# Power19V.net
KiCad netlist of a schematic drawn in Altium Designer
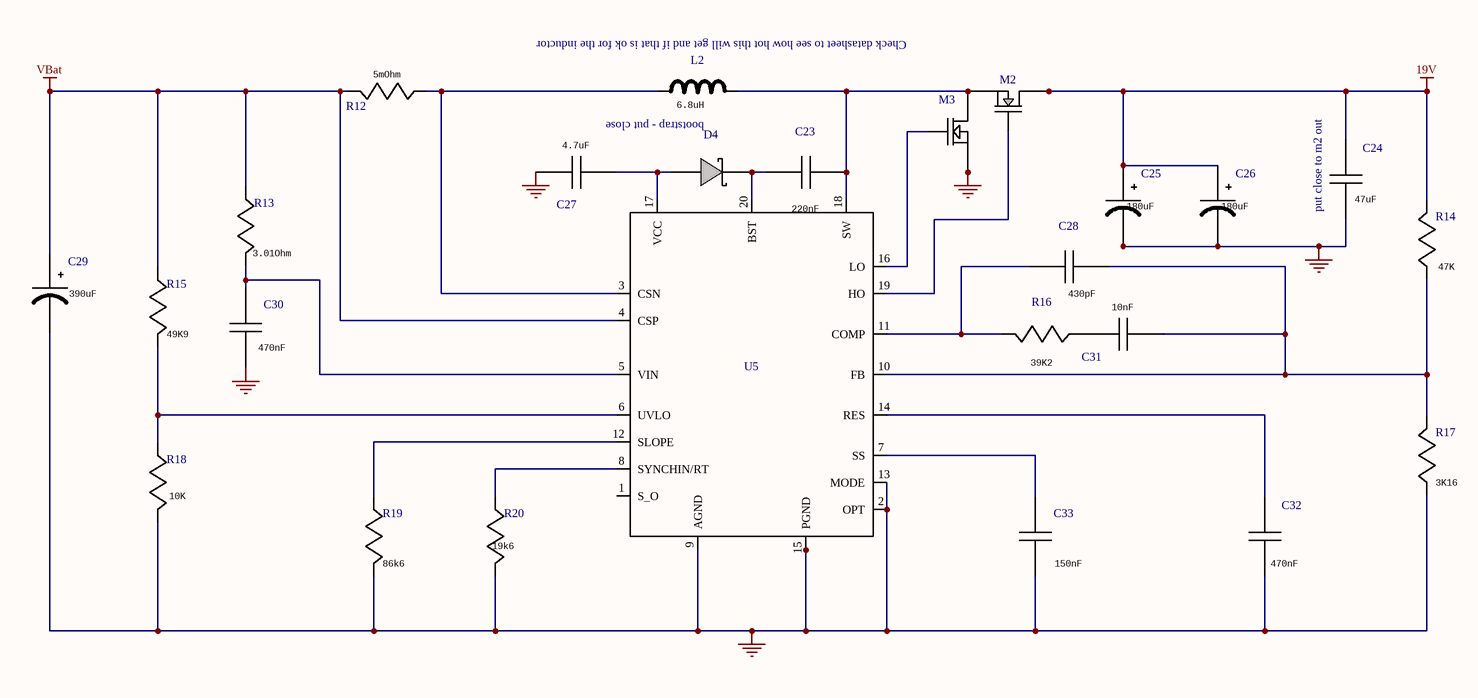
[diagram p0: Power19V.SchDoc]

(export (version "E")
  (design (tool "Eeschema 10.0.6"))
  (components
    (comp (ref "C23")
      (value "220nF")
      (footprint "1608")
      (description "Imported")
      (fields (field (name "MANUFACTURER_PART_NUMBER") "C0805C224K5RACTU"))
      (libsource (lib "TI WEBENCH") (part "C0805C224K5RACTU"))
    )
    (comp (ref "C24")
      (value "47uF")
      (footprint "1206")
      (description "Imported")
      (fields (field (name "MANUFACTURER_PART_NUMBER") "C3216JB1E476M"))
      (libsource (lib "TI WEBENCH") (part "C3216JB1E476M"))
    )
    (comp (ref "C25")
      (value "180uF")
      (footprint "CAPSMT_62_E12")
      (description "Imported")
      (fields (field (name "MANUFACTURER_PART_NUMBER") "25SVPF180M"))
      (libsource (lib "TI WEBENCH") (part "25SVPF180M"))
    )
    (comp (ref "C26")
      (value "180uF")
      (footprint "CAPSMT_62_E12")
      (description "Imported")
      (fields (field (name "MANUFACTURER_PART_NUMBER") "25SVPF180M"))
      (libsource (lib "TI WEBENCH") (part "25SVPF180M"))
    )
    (comp (ref "C27")
      (value "4.7uF")
      (footprint "1608")
      (description "Imported")
      (fields
        (field (name "MANUFACTURER_PART_NUMBER") "GRM21BC81E475KA12L")
        (field (name "Comment") "GRM21BC81E475KA1")
      )
      (libsource (lib "TI WEBENCH") (part "GRM21BC81E475KA1"))
    )
    (comp (ref "C28")
      (value "430pF")
      (footprint "1608")
      (description "Imported")
      (fields (field (name "MANUFACTURER_PART_NUMBER") "CL21C431JBANNNC"))
      (libsource (lib "TI WEBENCH") (part "CL21C431JBANNNC"))
    )
    (comp (ref "C29")
      (value "390uF")
      (footprint "CAPSMT_62_E12")
      (description "Imported")
      (fields (field (name "MANUFACTURER_PART_NUMBER") "20SVPF390M"))
      (libsource (lib "TI WEBENCH") (part "20SVPF390M"))
    )
    (comp (ref "C30")
      (value "470nF")
      (footprint "1608")
      (description "Imported")
      (fields
        (field (name "MANUFACTURER_PART_NUMBER") "GRM188R71C474KA88D")
        (field (name "Comment") "GRM188R71C474KA8")
      )
      (libsource (lib "TI WEBENCH") (part "GRM188R71C474KA8"))
    )
    (comp (ref "C31")
      (value "10nF")
      (footprint "1608")
      (description "Imported")
      (fields
        (field (name "MANUFACTURER_PART_NUMBER") "GRM216R71H103KA01D")
        (field (name "Comment") "GRM216R71H103KA0")
      )
      (libsource (lib "TI WEBENCH") (part "GRM216R71H103KA0"))
    )
    (comp (ref "C32")
      (value "470nF")
      (footprint "1608")
      (description "Imported")
      (fields (field (name "MANUFACTURER_PART_NUMBER") "TMK212BJ474KD-T"))
      (libsource (lib "TI WEBENCH") (part "TMK212BJ474KD-T"))
    )
    (comp (ref "C33")
      (value "150nF")
      (footprint "1608")
      (description "Imported")
      (fields
        (field (name "MANUFACTURER_PART_NUMBER") "GRM155R61A154KE19D")
        (field (name "Comment") "GRM155R61A154KE1")
      )
      (libsource (lib "TI WEBENCH") (part "GRM155R61A154KE1"))
    )
    (comp (ref "D4")
      (value "MBR130T1G")
      (footprint "SOD-123")
      (description "Imported")
      (libsource (lib "TI WEBENCH") (part "MBR130T1G"))
    )
    (comp (ref "L2")
      (value "6.8uH")
      (footprint "XAL1010")
      (description "Imported")
      (fields (field (name "MANUFACTURER_PART_NUMBER") "XAL1010-682MEB"))
      (libsource (lib "TI WEBENCH") (part "XAL1010-682MEB"))
    )
    (comp (ref "M2")
      (value "CSD16340Q3")
      (footprint "TRANS_NexFET_Q3")
      (description "Imported")
      (libsource (lib "TI WEBENCH") (part "CSD16340Q3"))
    )
    (comp (ref "M3")
      (value "BSZ035N03MS G")
      (footprint "PG-TSDSON-8")
      (description "Imported")
      (libsource (lib "TI WEBENCH") (part "BSZ035N03MS G"))
    )
    (comp (ref "R12")
      (value "5mOhm")
      (footprint "1608")
      (description "Imported")
      (fields
        (field (name "MANUFACTURER_PART_NUMBER") "PRL1632-R005-F-T1")
        (field (name "Comment") "PRL1632-R005-F-T")
      )
      (libsource (lib "TI WEBENCH") (part "PRL1632-R005-F-T"))
    )
    (comp (ref "R13")
      (value "3.01Ohm")
      (footprint "1608")
      (description "Imported")
      (fields (field (name "MANUFACTURER_PART_NUMBER") "CRCW08053R01FKEA"))
      (libsource (lib "TI WEBENCH") (part "CRCW08053R01FKEA"))
    )
    (comp (ref "R14")
      (value "47K")
      (footprint "1608")
      (description "Imported")
      (fields (field (name "MANUFACTURER_PART_NUMBER") "RR1220P-473-D"))
      (libsource (lib "TI WEBENCH") (part "RR1220P-473-D"))
    )
    (comp (ref "R15")
      (value "49K9")
      (footprint "1608")
      (description "Imported")
      (fields (field (name "MANUFACTURER_PART_NUMBER") "CRCW040249K9FKED"))
      (libsource (lib "TI WEBENCH") (part "CRCW040249K9FKED"))
    )
    (comp (ref "R16")
      (value "39K2")
      (footprint "1608")
      (description "Imported")
      (fields (field (name "MANUFACTURER_PART_NUMBER") "CRCW040239K2FKED"))
      (libsource (lib "TI WEBENCH") (part "CRCW040239K2FKED"))
    )
    (comp (ref "R17")
      (value "3K16")
      (footprint "1608")
      (description "Imported")
      (fields (field (name "MANUFACTURER_PART_NUMBER") "CRCW04023K16FKED"))
      (libsource (lib "TI WEBENCH") (part "CRCW04023K16FKED"))
    )
    (comp (ref "R18")
      (value "10K")
      (footprint "1608")
      (description "Imported")
      (fields (field (name "MANUFACTURER_PART_NUMBER") "CRCW040210K0FKED"))
      (libsource (lib "TI WEBENCH") (part "CRCW040210K0FKED"))
    )
    (comp (ref "R19")
      (value "86k6")
      (footprint "1608")
      (description "Imported")
      (fields (field (name "MANUFACTURER_PART_NUMBER") "CRCW040286K6FKED"))
      (libsource (lib "TI WEBENCH") (part "CRCW040286K6FKED"))
    )
    (comp (ref "R20")
      (value "19k6")
      (footprint "1608")
      (description "Imported")
      (fields (field (name "MANUFACTURER_PART_NUMBER") "CRCW040219K6FKED"))
      (libsource (lib "TI WEBENCH") (part "CRCW040219K6FKED"))
    )
    (comp (ref "U5")
      (value "LM5122MH/NOPB")
      (footprint "MXA20A")
      (description "Imported")
      (libsource (lib "TI WEBENCH") (part "LM5122MH/NOPB"))
    )
  )
  (nets
    (net (code "1") (name "19V") (class "Default")
      (node (ref "C24") (pin "1") (pinfunction "1_1") (pintype "passive"))
      (node (ref "C25") (pin "1") (pinfunction "+_1") (pintype "passive"))
      (node (ref "C26") (pin "1") (pinfunction "+_1") (pintype "passive"))
      (node (ref "M2") (pin "5") (pinfunction "Drain_5") (pintype "passive"))
      (node (ref "M2") (pin "6") (pinfunction "Drain_6") (pintype "passive"))
      (node (ref "M2") (pin "7") (pinfunction "Drain_7") (pintype "passive"))
      (node (ref "M2") (pin "8") (pinfunction "Drain_8") (pintype "passive"))
      (node (ref "M2") (pin "9") (pinfunction "Drain_9") (pintype "passive"))
      (node (ref "R14") (pin "1") (pinfunction "1_1") (pintype "passive"))
    )
    (net (code "2") (name "GND") (class "Default")
      (node (ref "C24") (pin "2") (pinfunction "2_2") (pintype "passive"))
      (node (ref "C25") (pin "2") (pinfunction "-_2") (pintype "passive"))
      (node (ref "C26") (pin "2") (pinfunction "-_2") (pintype "passive"))
      (node (ref "C27") (pin "1") (pinfunction "1_1") (pintype "passive"))
      (node (ref "C29") (pin "2") (pinfunction "-_2") (pintype "passive"))
      (node (ref "C30") (pin "2") (pinfunction "2_2") (pintype "passive"))
      (node (ref "C32") (pin "2") (pinfunction "2_2") (pintype "passive"))
      (node (ref "C33") (pin "2") (pinfunction "2_2") (pintype "passive"))
      (node (ref "M3") (pin "1") (pinfunction "Source_1") (pintype "passive"))
      (node (ref "M3") (pin "2") (pinfunction "Source_2") (pintype "passive"))
      (node (ref "M3") (pin "3") (pinfunction "Source_3") (pintype "passive"))
      (node (ref "R17") (pin "2") (pinfunction "2_2") (pintype "passive"))
      (node (ref "R18") (pin "1") (pinfunction "1_1") (pintype "passive"))
      (node (ref "R19") (pin "1") (pinfunction "1_1") (pintype "passive"))
      (node (ref "R20") (pin "1") (pinfunction "1_1") (pintype "passive"))
      (node (ref "U5") (pin "13") (pinfunction "MODE_13") (pintype "passive"))
      (node (ref "U5") (pin "15") (pinfunction "PGND_15") (pintype "passive"))
      (node (ref "U5") (pin "2") (pinfunction "OPT_2") (pintype "passive"))
      (node (ref "U5") (pin "21") (pinfunction "PGND_21") (pintype "passive"))
      (node (ref "U5") (pin "9") (pinfunction "AGND_9") (pintype "passive"))
    )
    (net (code "3") (name "Net-(C31-Pad2)") (class "Default")
      (node (ref "C31") (pin "2") (pinfunction "2_2") (pintype "passive"))
      (node (ref "R16") (pin "2") (pinfunction "2_2") (pintype "passive"))
    )
    (net (code "4") (name "Net-(D4-A)") (class "Default")
      (node (ref "C27") (pin "2") (pinfunction "2_2") (pintype "passive"))
      (node (ref "D4") (pin "2") (pinfunction "A_2") (pintype "passive"))
      (node (ref "U5") (pin "17") (pinfunction "VCC_17") (pintype "passive"))
    )
    (net (code "5") (name "Net-(D4-K)") (class "Default")
      (node (ref "C23") (pin "1") (pinfunction "1_1") (pintype "passive"))
      (node (ref "D4") (pin "1") (pinfunction "K_1") (pintype "passive"))
      (node (ref "U5") (pin "20") (pinfunction "BST_20") (pintype "passive"))
    )
    (net (code "6") (name "Net-(M2-Gate)") (class "Default")
      (node (ref "M2") (pin "4") (pinfunction "Gate_4") (pintype "passive"))
      (node (ref "U5") (pin "19") (pinfunction "HO_19") (pintype "passive"))
    )
    (net (code "7") (name "Net-(M3-Gate)") (class "Default")
      (node (ref "M3") (pin "4") (pinfunction "Gate_4") (pintype "passive"))
      (node (ref "U5") (pin "16") (pinfunction "LO_16") (pintype "passive"))
    )
    (net (code "8") (name "Net-(U5-COMP)") (class "Default")
      (node (ref "C28") (pin "2") (pinfunction "2_2") (pintype "passive"))
      (node (ref "R16") (pin "1") (pinfunction "1_1") (pintype "passive"))
      (node (ref "U5") (pin "11") (pinfunction "COMP_11") (pintype "passive"))
    )
    (net (code "9") (name "Net-(U5-CSN)") (class "Default")
      (node (ref "L2") (pin "1") (pinfunction "1_1") (pintype "passive"))
      (node (ref "R12") (pin "2") (pinfunction "2_2") (pintype "passive"))
      (node (ref "U5") (pin "3") (pinfunction "CSN_3") (pintype "passive"))
    )
    (net (code "10") (name "Net-(U5-FB)") (class "Default")
      (node (ref "C28") (pin "1") (pinfunction "1_1") (pintype "passive"))
      (node (ref "C31") (pin "1") (pinfunction "1_1") (pintype "passive"))
      (node (ref "R14") (pin "2") (pinfunction "2_2") (pintype "passive"))
      (node (ref "R17") (pin "1") (pinfunction "1_1") (pintype "passive"))
      (node (ref "U5") (pin "10") (pinfunction "FB_10") (pintype "passive"))
    )
    (net (code "11") (name "Net-(U5-RES)") (class "Default")
      (node (ref "C32") (pin "1") (pinfunction "1_1") (pintype "passive"))
      (node (ref "U5") (pin "14") (pinfunction "RES_14") (pintype "passive"))
    )
    (net (code "12") (name "Net-(U5-SLOPE)") (class "Default")
      (node (ref "R19") (pin "2") (pinfunction "2_2") (pintype "passive"))
      (node (ref "U5") (pin "12") (pinfunction "SLOPE_12") (pintype "passive"))
    )
    (net (code "13") (name "Net-(U5-SS)") (class "Default")
      (node (ref "C33") (pin "1") (pinfunction "1_1") (pintype "passive"))
      (node (ref "U5") (pin "7") (pinfunction "SS_7") (pintype "passive"))
    )
    (net (code "14") (name "Net-(U5-SW)") (class "Default")
      (node (ref "C23") (pin "2") (pinfunction "2_2") (pintype "passive"))
      (node (ref "L2") (pin "2") (pinfunction "2_2") (pintype "passive"))
      (node (ref "M2") (pin "1") (pinfunction "Source_1") (pintype "passive"))
      (node (ref "M2") (pin "2") (pinfunction "Source_2") (pintype "passive"))
      (node (ref "M2") (pin "3") (pinfunction "Source_3") (pintype "passive"))
      (node (ref "M3") (pin "5") (pinfunction "Drain_5") (pintype "passive"))
      (node (ref "M3") (pin "6") (pinfunction "Drain_6") (pintype "passive"))
      (node (ref "M3") (pin "7") (pinfunction "Drain_7") (pintype "passive"))
      (node (ref "M3") (pin "8") (pinfunction "Drain_8") (pintype "passive"))
      (node (ref "M3") (pin "9") (pinfunction "Drain_9") (pintype "passive"))
      (node (ref "U5") (pin "18") (pinfunction "SW_18") (pintype "passive"))
    )
    (net (code "15") (name "Net-(U5-SYNCHIN{slash}RT)") (class "Default")
      (node (ref "R20") (pin "2") (pinfunction "2_2") (pintype "passive"))
      (node (ref "U5") (pin "8") (pinfunction "SYNCHIN/RT_8") (pintype "passive"))
    )
    (net (code "16") (name "Net-(U5-UVLO)") (class "Default")
      (node (ref "R15") (pin "1") (pinfunction "1_1") (pintype "passive"))
      (node (ref "R18") (pin "2") (pinfunction "2_2") (pintype "passive"))
      (node (ref "U5") (pin "6") (pinfunction "UVLO_6") (pintype "passive"))
    )
    (net (code "17") (name "Net-(U5-VIN)") (class "Default")
      (node (ref "C30") (pin "1") (pinfunction "1_1") (pintype "passive"))
      (node (ref "R13") (pin "1") (pinfunction "1_1") (pintype "passive"))
      (node (ref "U5") (pin "5") (pinfunction "VIN_5") (pintype "passive"))
    )
    (net (code "18") (name "VBat") (class "Default")
      (node (ref "C29") (pin "1") (pinfunction "+_1") (pintype "passive"))
      (node (ref "R12") (pin "1") (pinfunction "1_1") (pintype "passive"))
      (node (ref "R13") (pin "2") (pinfunction "2_2") (pintype "passive"))
      (node (ref "R15") (pin "2") (pinfunction "2_2") (pintype "passive"))
      (node (ref "U5") (pin "4") (pinfunction "CSP_4") (pintype "passive"))
    )
    (net (code "19") (name "unconnected-(U5-S_O-Pad1)") (class "Default")
      (node (ref "U5") (pin "1") (pinfunction "S_O_1") (pintype "passive"))
    )
  )
)
